# v0_1_0.net
KiCad netlist of a schematic drawn in EAGLE
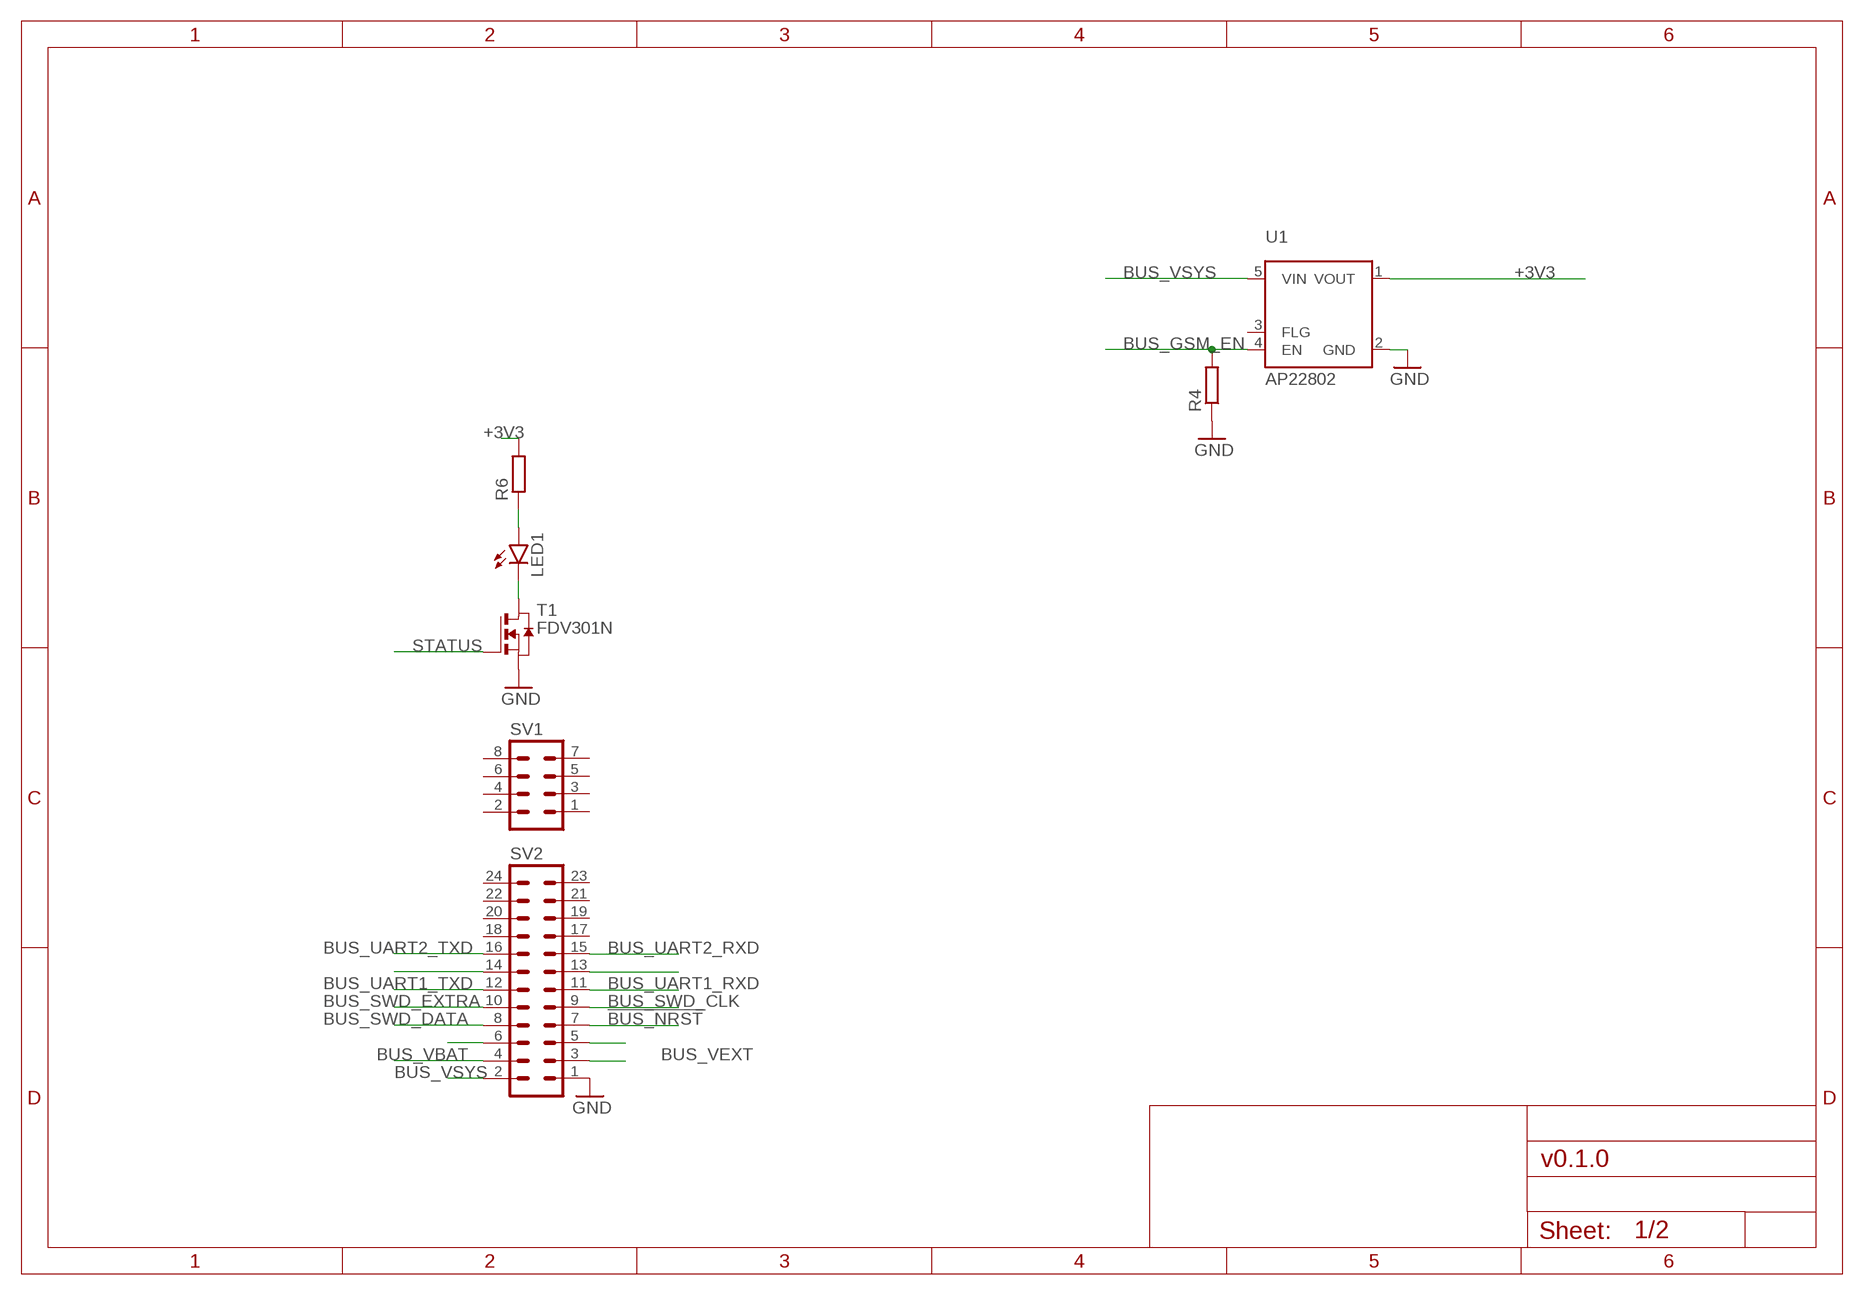
[diagram p0: schematic, sheet 1]
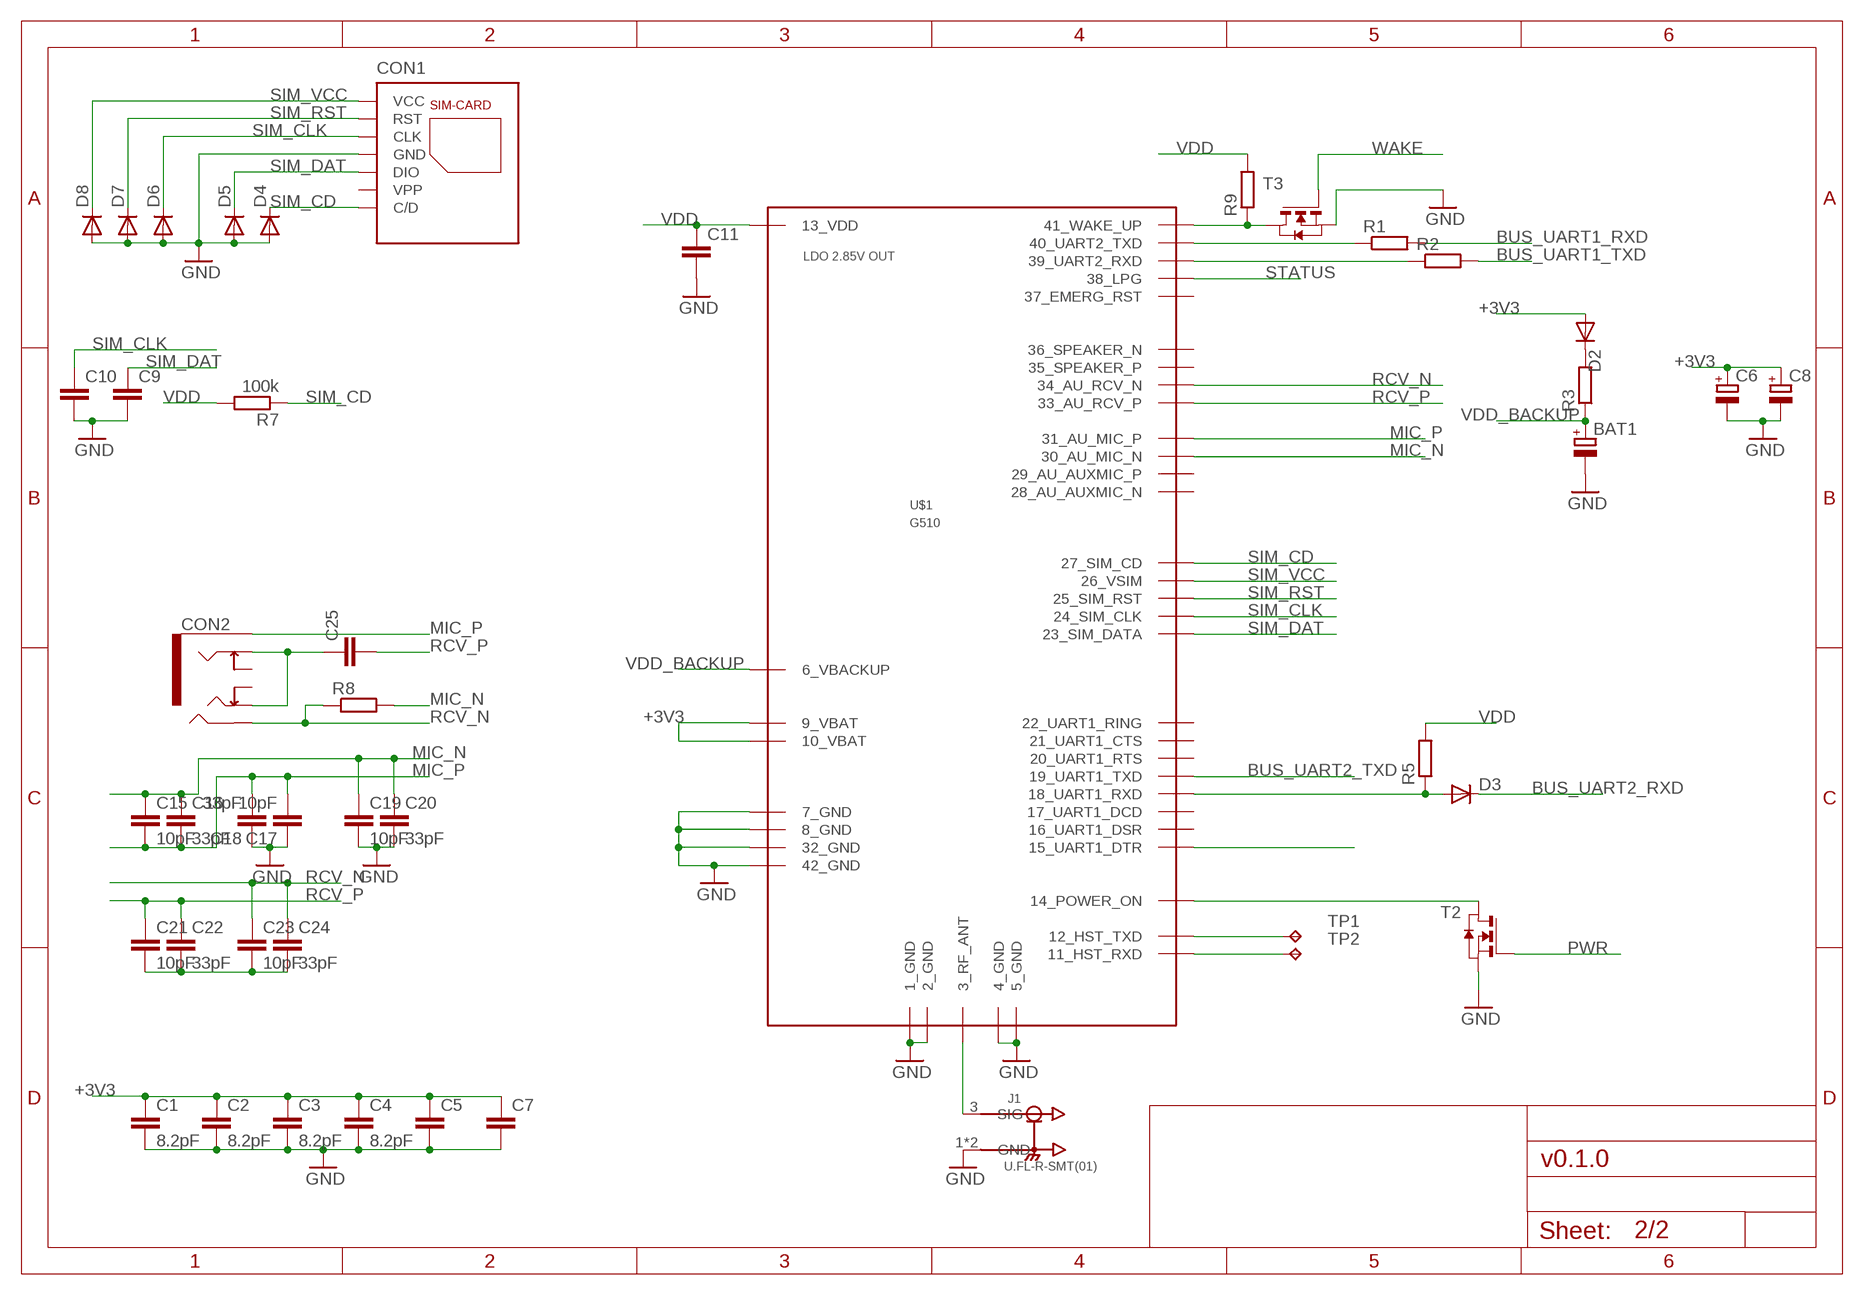
[diagram p1: schematic, sheet 2]

(export (version "E")
  (design (tool "Eeschema 10.0.6"))
  (components
    (comp (ref "LED1")
      (value "LEDCHIP-LED0603")
      (footprint "eagle-import:CHIP-LED0603")
      (libsource (lib "eagle-import") (part "LEDCHIP-LED0603"))
    )
    (comp (ref "R4")
      (value "R-EU_R0402")
      (footprint "eagle-import:R0402")
      (libsource (lib "eagle-import") (part "R-EU_R0402"))
    )
    (comp (ref "R6")
      (value "R-EU_R0402")
      (footprint "eagle-import:R0402")
      (libsource (lib "eagle-import") (part "R-EU_R0402"))
    )
    (comp (ref "SV1")
      (value "MA04-2")
      (footprint "eagle-import:MA04-2")
      (libsource (lib "eagle-import") (part "MA04-2"))
    )
    (comp (ref "SV2")
      (value "MA12-2")
      (footprint "eagle-import:MA12-2")
      (libsource (lib "eagle-import") (part "MA12-2"))
    )
    (comp (ref "T1")
      (value "FDV301N")
      (footprint "eagle-import:SOT-23")
      (libsource (lib "eagle-import") (part "NMOSSOT23"))
    )
    (comp (ref "U1")
      (value "AP22802")
      (footprint "eagle-import:SOT25")
      (libsource (lib "eagle-import") (part "AP22802"))
    )
    (comp (ref "BAT1")
      (value "DCK-3R3E224U-E")
      (footprint "eagle-import:621")
      (libsource (lib "eagle-import") (part "DCK-3R3E224U-E"))
    )
    (comp (ref "C1")
      (value "8.2pF")
      (footprint "eagle-import:C0402")
      (libsource (lib "eagle-import") (part "C-EUC0402"))
    )
    (comp (ref "C2")
      (value "8.2pF")
      (footprint "eagle-import:C0402")
      (libsource (lib "eagle-import") (part "C-EUC0402"))
    )
    (comp (ref "C3")
      (value "8.2pF")
      (footprint "eagle-import:C0402")
      (libsource (lib "eagle-import") (part "C-EUC0402"))
    )
    (comp (ref "C4")
      (value "8.2pF")
      (footprint "eagle-import:C0402")
      (libsource (lib "eagle-import") (part "C-EUC0402"))
    )
    (comp (ref "C5")
      (value "C-EUC0603")
      (footprint "eagle-import:C0603")
      (libsource (lib "eagle-import") (part "C-EUC0603"))
    )
    (comp (ref "C6")
      (value "CPOL-EUSMCC")
      (footprint "eagle-import:SMC_C")
      (libsource (lib "eagle-import") (part "CPOL-EUSMCC"))
    )
    (comp (ref "C7")
      (value "C-EUC0603")
      (footprint "eagle-import:C0603")
      (libsource (lib "eagle-import") (part "C-EUC0603"))
    )
    (comp (ref "C8")
      (value "CPOL-EUSMCC")
      (footprint "eagle-import:SMC_C")
      (libsource (lib "eagle-import") (part "CPOL-EUSMCC"))
    )
    (comp (ref "C9")
      (value "C-EUC0402")
      (footprint "eagle-import:C0402")
      (libsource (lib "eagle-import") (part "C-EUC0402"))
    )
    (comp (ref "C10")
      (value "C-EUC0402")
      (footprint "eagle-import:C0402")
      (libsource (lib "eagle-import") (part "C-EUC0402"))
    )
    (comp (ref "C11")
      (value "C-EUC0402")
      (footprint "eagle-import:C0402")
      (libsource (lib "eagle-import") (part "C-EUC0402"))
    )
    (comp (ref "C15")
      (value "10pF")
      (footprint "eagle-import:C0402")
      (libsource (lib "eagle-import") (part "C-EUC0402"))
    )
    (comp (ref "C16")
      (value "33pF")
      (footprint "eagle-import:C0402")
      (libsource (lib "eagle-import") (part "C-EUC0402"))
    )
    (comp (ref "C17")
      (value "10pF")
      (footprint "eagle-import:C0402")
      (libsource (lib "eagle-import") (part "C-EUC0402"))
    )
    (comp (ref "C18")
      (value "33pF")
      (footprint "eagle-import:C0402")
      (libsource (lib "eagle-import") (part "C-EUC0402"))
    )
    (comp (ref "C19")
      (value "10pF")
      (footprint "eagle-import:C0402")
      (libsource (lib "eagle-import") (part "C-EUC0402"))
    )
    (comp (ref "C20")
      (value "33pF")
      (footprint "eagle-import:C0402")
      (libsource (lib "eagle-import") (part "C-EUC0402"))
    )
    (comp (ref "C21")
      (value "10pF")
      (footprint "eagle-import:C0402")
      (libsource (lib "eagle-import") (part "C-EUC0402"))
    )
    (comp (ref "C22")
      (value "33pF")
      (footprint "eagle-import:C0402")
      (libsource (lib "eagle-import") (part "C-EUC0402"))
    )
    (comp (ref "C23")
      (value "10pF")
      (footprint "eagle-import:C0402")
      (libsource (lib "eagle-import") (part "C-EUC0402"))
    )
    (comp (ref "C24")
      (value "33pF")
      (footprint "eagle-import:C0402")
      (libsource (lib "eagle-import") (part "C-EUC0402"))
    )
    (comp (ref "C25")
      (value "C-EUC0603")
      (footprint "eagle-import:C0603")
      (libsource (lib "eagle-import") (part "C-EUC0603"))
    )
    (comp (ref "CON1")
      (value "115Q-BCA0")
      (footprint "eagle-import:115Q")
      (libsource (lib "eagle-import") (part "115Q-BCA0"))
    )
    (comp (ref "CON2")
      (value "1503-21")
      (footprint "eagle-import:150321")
      (libsource (lib "eagle-import") (part "1503-21"))
    )
    (comp (ref "D2")
      (value "DIODE-SOD323-R")
      (footprint "eagle-import:SOD323-R")
      (libsource (lib "eagle-import") (part "DIODE-SOD323-R"))
    )
    (comp (ref "D3")
      (value "DIODE-SOD323-R")
      (footprint "eagle-import:SOD323-R")
      (libsource (lib "eagle-import") (part "DIODE-SOD323-R"))
    )
    (comp (ref "D4")
      (value "DIODE-SOD323-R")
      (footprint "eagle-import:SOD323-R")
      (libsource (lib "eagle-import") (part "DIODE-SOD323-R"))
    )
    (comp (ref "D5")
      (value "DIODE-SOD323-R")
      (footprint "eagle-import:SOD323-R")
      (libsource (lib "eagle-import") (part "DIODE-SOD323-R"))
    )
    (comp (ref "D6")
      (value "DIODE-SOD323-R")
      (footprint "eagle-import:SOD323-R")
      (libsource (lib "eagle-import") (part "DIODE-SOD323-R"))
    )
    (comp (ref "D7")
      (value "DIODE-SOD323-R")
      (footprint "eagle-import:SOD323-R")
      (libsource (lib "eagle-import") (part "DIODE-SOD323-R"))
    )
    (comp (ref "D8")
      (value "DIODE-SOD323-R")
      (footprint "eagle-import:SOD323-R")
      (libsource (lib "eagle-import") (part "DIODE-SOD323-R"))
    )
    (comp (ref "J1")
      (value "U.FL-R-SMT(01)")
      (footprint "eagle-import:HRS_U.FL-R-SMT(01)")
      (fields (field (name "MF") "Hirose") (field (name "MP") "U.FL-R-SMT_01_"))
      (libsource (lib "eagle-import") (part "U.FL-R-SMT(01)"))
    )
    (comp (ref "R1")
      (value "R-EU_R0402")
      (footprint "eagle-import:R0402")
      (libsource (lib "eagle-import") (part "R-EU_R0402"))
    )
    (comp (ref "R2")
      (value "R-EU_R0402")
      (footprint "eagle-import:R0402")
      (libsource (lib "eagle-import") (part "R-EU_R0402"))
    )
    (comp (ref "R3")
      (value "R-EU_R0402")
      (footprint "eagle-import:R0402")
      (libsource (lib "eagle-import") (part "R-EU_R0402"))
    )
    (comp (ref "R5")
      (value "R-EU_R0402")
      (footprint "eagle-import:R0402")
      (libsource (lib "eagle-import") (part "R-EU_R0402"))
    )
    (comp (ref "R7")
      (value "100k")
      (footprint "eagle-import:R0402")
      (libsource (lib "eagle-import") (part "R-EU_R0402"))
    )
    (comp (ref "R8")
      (value "R-EU_R0402")
      (footprint "eagle-import:R0402")
      (libsource (lib "eagle-import") (part "R-EU_R0402"))
    )
    (comp (ref "R9")
      (value "R-EU_R0402")
      (footprint "eagle-import:R0402")
      (libsource (lib "eagle-import") (part "R-EU_R0402"))
    )
    (comp (ref "T2")
      (value "NMOSSOT23")
      (footprint "eagle-import:SOT-23")
      (libsource (lib "eagle-import") (part "NMOSSOT23"))
    )
    (comp (ref "T3")
      (value "NMOSSOT23")
      (footprint "eagle-import:SOT-23")
      (libsource (lib "eagle-import") (part "NMOSSOT23"))
    )
    (comp (ref "TP1")
      (value "TPB1,27")
      (footprint "eagle-import:B1,27")
      (libsource (lib "eagle-import") (part "TPB1,27"))
    )
    (comp (ref "TP2")
      (value "TPB1,27")
      (footprint "eagle-import:B1,27")
      (libsource (lib "eagle-import") (part "TPB1,27"))
    )
    (comp (ref "U$1")
      (value "G510")
      (footprint "eagle-import:G510")
      (libsource (lib "eagle-import") (part "G510"))
    )
  )
  (nets
    (net (code "1") (name "+3V3") (class "Default")
      (node (ref "C1") (pin "1") (pinfunction "1_1") (pintype "passive"))
      (node (ref "C2") (pin "1") (pinfunction "1_1") (pintype "passive"))
      (node (ref "C3") (pin "1") (pinfunction "1_1") (pintype "passive"))
      (node (ref "C4") (pin "1") (pinfunction "1_1") (pintype "passive"))
      (node (ref "C5") (pin "1") (pinfunction "1_1") (pintype "passive"))
      (node (ref "C6") (pin "+") (pinfunction "+_+") (pintype "passive"))
      (node (ref "C7") (pin "1") (pinfunction "1_1") (pintype "passive"))
      (node (ref "C8") (pin "+") (pinfunction "+_+") (pintype "passive"))
      (node (ref "D2") (pin "A") (pinfunction "A_A") (pintype "passive"))
      (node (ref "R6") (pin "2") (pinfunction "2_2") (pintype "passive"))
      (node (ref "U$1") (pin "10_VBAT") (pinfunction "10_VBAT_10_VBAT") (pintype "power_in"))
      (node (ref "U$1") (pin "9_VBAT") (pinfunction "9_VBAT_9_VBAT") (pintype "power_in"))
      (node (ref "U1") (pin "1") (pinfunction "VOUT_1") (pintype "bidirectional"))
    )
    (net (code "2") (name "BUS_GSM_EN") (class "Default")
      (node (ref "R4") (pin "2") (pinfunction "2_2") (pintype "passive"))
      (node (ref "U1") (pin "4") (pinfunction "EN_4") (pintype "bidirectional"))
    )
    (net (code "3") (name "BUS_SWD_CLK") (class "Default")
      (node (ref "SV2") (pin "9") (pinfunction "9_9") (pintype "passive"))
    )
    (net (code "4") (name "BUS_SWD_DATA") (class "Default")
      (node (ref "SV2") (pin "8") (pinfunction "8_8") (pintype "passive"))
    )
    (net (code "5") (name "BUS_SWD_EXTRA") (class "Default")
      (node (ref "SV2") (pin "10") (pinfunction "10_10") (pintype "passive"))
    )
    (net (code "6") (name "BUS_UART1_RXD") (class "Default")
      (node (ref "R1") (pin "2") (pinfunction "2_2") (pintype "passive"))
      (node (ref "SV2") (pin "11") (pinfunction "11_11") (pintype "passive"))
    )
    (net (code "7") (name "BUS_UART1_TXD") (class "Default")
      (node (ref "R2") (pin "2") (pinfunction "2_2") (pintype "passive"))
      (node (ref "SV2") (pin "12") (pinfunction "12_12") (pintype "passive"))
    )
    (net (code "8") (name "BUS_UART2_RXD") (class "Default")
      (node (ref "D3") (pin "C") (pinfunction "C_C") (pintype "passive"))
      (node (ref "SV2") (pin "15") (pinfunction "15_15") (pintype "passive"))
    )
    (net (code "9") (name "BUS_UART2_TXD") (class "Default")
      (node (ref "SV2") (pin "16") (pinfunction "16_16") (pintype "passive"))
      (node (ref "U$1") (pin "19_UART1_TXD") (pinfunction "19_UART1_TXD_19_UART1_TXD") (pintype "output"))
    )
    (net (code "10") (name "BUS_VBAT") (class "Default")
      (node (ref "SV2") (pin "4") (pinfunction "4_4") (pintype "passive"))
    )
    (net (code "11") (name "BUS_VEXT") (class "Default")
      (node (ref "SV2") (pin "3") (pinfunction "3_3") (pintype "passive"))
    )
    (net (code "12") (name "BUS_VSYS") (class "Default")
      (node (ref "SV2") (pin "2") (pinfunction "2_2") (pintype "passive"))
      (node (ref "U1") (pin "5") (pinfunction "VIN_5") (pintype "bidirectional"))
    )
    (net (code "13") (name "GND") (class "Default")
      (node (ref "BAT1") (pin "-") (pinfunction "-_-") (pintype "passive"))
      (node (ref "C1") (pin "2") (pinfunction "2_2") (pintype "passive"))
      (node (ref "C10") (pin "2") (pinfunction "2_2") (pintype "passive"))
      (node (ref "C11") (pin "2") (pinfunction "2_2") (pintype "passive"))
      (node (ref "C17") (pin "1") (pinfunction "1_1") (pintype "passive"))
      (node (ref "C18") (pin "1") (pinfunction "1_1") (pintype "passive"))
      (node (ref "C19") (pin "2") (pinfunction "2_2") (pintype "passive"))
      (node (ref "C2") (pin "2") (pinfunction "2_2") (pintype "passive"))
      (node (ref "C20") (pin "2") (pinfunction "2_2") (pintype "passive"))
      (node (ref "C3") (pin "2") (pinfunction "2_2") (pintype "passive"))
      (node (ref "C4") (pin "2") (pinfunction "2_2") (pintype "passive"))
      (node (ref "C5") (pin "2") (pinfunction "2_2") (pintype "passive"))
      (node (ref "C6") (pin "-") (pinfunction "-_-") (pintype "passive"))
      (node (ref "C7") (pin "2") (pinfunction "2_2") (pintype "passive"))
      (node (ref "C8") (pin "-") (pinfunction "-_-") (pintype "passive"))
      (node (ref "C9") (pin "2") (pinfunction "2_2") (pintype "passive"))
      (node (ref "CON1") (pin "GND1") (pinfunction "GND_GND1") (pintype "passive"))
      (node (ref "CON1") (pin "GND2") (pinfunction "GND_GND2") (pintype "passive"))
      (node (ref "CON1") (pin "GND3") (pinfunction "GND_GND3") (pintype "passive"))
      (node (ref "CON1") (pin "GND4") (pinfunction "GND_GND4") (pintype "passive"))
      (node (ref "CON1") (pin "P5") (pinfunction "GND_P5") (pintype "passive"))
      (node (ref "D4") (pin "A") (pinfunction "A_A") (pintype "passive"))
      (node (ref "D5") (pin "A") (pinfunction "A_A") (pintype "passive"))
      (node (ref "D6") (pin "A") (pinfunction "A_A") (pintype "passive"))
      (node (ref "D7") (pin "A") (pinfunction "A_A") (pintype "passive"))
      (node (ref "D8") (pin "A") (pinfunction "A_A") (pintype "passive"))
      (node (ref "J1") (pin "1") (pinfunction "GND_1") (pintype "passive"))
      (node (ref "J1") (pin "2") (pinfunction "GND_2") (pintype "passive"))
      (node (ref "R4") (pin "1") (pinfunction "1_1") (pintype "passive"))
      (node (ref "SV2") (pin "1") (pinfunction "1_1") (pintype "passive"))
      (node (ref "T1") (pin "2") (pinfunction "S_2") (pintype "passive"))
      (node (ref "T2") (pin "2") (pinfunction "S_2") (pintype "passive"))
      (node (ref "T3") (pin "2") (pinfunction "S_2") (pintype "passive"))
      (node (ref "U$1") (pin "1_GND") (pinfunction "1_GND_1_GND") (pintype "power_in"))
      (node (ref "U$1") (pin "2_GND") (pinfunction "2_GND_2_GND") (pintype "power_in"))
      (node (ref "U$1") (pin "32_GND") (pinfunction "32_GND_32_GND") (pintype "power_in"))
      (node (ref "U$1") (pin "42_GND") (pinfunction "42_GND_42_GND") (pintype "power_in"))
      (node (ref "U$1") (pin "4_GND") (pinfunction "4_GND_4_GND") (pintype "power_in"))
      (node (ref "U$1") (pin "5_GND") (pinfunction "5_GND_5_GND") (pintype "power_in"))
      (node (ref "U$1") (pin "7_GND") (pinfunction "7_GND_7_GND") (pintype "power_in"))
      (node (ref "U$1") (pin "8_GND") (pinfunction "8_GND_8_GND") (pintype "power_in"))
      (node (ref "U1") (pin "2") (pinfunction "GND_2") (pintype "bidirectional"))
    )
    (net (code "14") (name "MIC_N") (class "Default")
      (node (ref "C15") (pin "1") (pinfunction "1_1") (pintype "passive"))
      (node (ref "C16") (pin "1") (pinfunction "1_1") (pintype "passive"))
      (node (ref "C19") (pin "1") (pinfunction "1_1") (pintype "passive"))
      (node (ref "C20") (pin "1") (pinfunction "1_1") (pintype "passive"))
      (node (ref "R8") (pin "2") (pinfunction "2_2") (pintype "passive"))
      (node (ref "U$1") (pin "30_AU_MIC_N") (pinfunction "30_AU_MIC_N_30_AU_MIC_N") (pintype "bidirectional"))
    )
    (net (code "15") (name "MIC_P") (class "Default")
      (node (ref "C15") (pin "2") (pinfunction "2_2") (pintype "passive"))
      (node (ref "C16") (pin "2") (pinfunction "2_2") (pintype "passive"))
      (node (ref "C17") (pin "2") (pinfunction "2_2") (pintype "passive"))
      (node (ref "C18") (pin "2") (pinfunction "2_2") (pintype "passive"))
      (node (ref "CON2") (pin "1") (pinfunction "1_1") (pintype "bidirectional"))
      (node (ref "U$1") (pin "31_AU_MIC_P") (pinfunction "31_AU_MIC_P_31_AU_MIC_P") (pintype "bidirectional"))
    )
    (net (code "16") (name "Net-(C21-Pad2)") (class "Default")
      (node (ref "C21") (pin "2") (pinfunction "2_2") (pintype "passive"))
      (node (ref "C22") (pin "2") (pinfunction "2_2") (pintype "passive"))
      (node (ref "C23") (pin "2") (pinfunction "2_2") (pintype "passive"))
      (node (ref "C24") (pin "2") (pinfunction "2_2") (pintype "passive"))
    )
    (net (code "17") (name "Net-(C25-Pad1)") (class "Default")
      (node (ref "C25") (pin "1") (pinfunction "1_1") (pintype "passive"))
      (node (ref "CON2") (pin "3") (pinfunction "3_3") (pintype "bidirectional"))
      (node (ref "CON2") (pin "5") (pinfunction "5_5") (pintype "bidirectional"))
    )
    (net (code "18") (name "Net-(D2-PadC)") (class "Default")
      (node (ref "D2") (pin "C") (pinfunction "C_C") (pintype "passive"))
      (node (ref "R3") (pin "2") (pinfunction "2_2") (pintype "passive"))
    )
    (net (code "19") (name "Net-(D3-PadA)") (class "Default")
      (node (ref "D3") (pin "A") (pinfunction "A_A") (pintype "passive"))
      (node (ref "R5") (pin "1") (pinfunction "1_1") (pintype "passive"))
      (node (ref "U$1") (pin "18_UART1_RXD") (pinfunction "18_UART1_RXD_18_UART1_RXD") (pintype "input"))
    )
    (net (code "20") (name "Net-(J1-SIG)") (class "Default")
      (node (ref "J1") (pin "3") (pinfunction "SIG_3") (pintype "passive"))
      (node (ref "U$1") (pin "3_RF_ANT") (pinfunction "3_RF_ANT_3_RF_ANT") (pintype "bidirectional"))
    )
    (net (code "21") (name "Net-(LED1-PadA)") (class "Default")
      (node (ref "LED1") (pin "A") (pinfunction "A_A") (pintype "passive"))
      (node (ref "R6") (pin "1") (pinfunction "1_1") (pintype "passive"))
    )
    (net (code "22") (name "Net-(R1-Pad1)") (class "Default")
      (node (ref "R1") (pin "1") (pinfunction "1_1") (pintype "passive"))
      (node (ref "U$1") (pin "40_UART2_TXD") (pinfunction "40_UART2_TXD_40_UART2_TXD") (pintype "output"))
    )
    (net (code "23") (name "Net-(R2-Pad1)") (class "Default")
      (node (ref "R2") (pin "1") (pinfunction "1_1") (pintype "passive"))
      (node (ref "U$1") (pin "39_UART2_RXD") (pinfunction "39_UART2_RXD_39_UART2_RXD") (pintype "input"))
    )
    (net (code "24") (name "Net-(T1-D)") (class "Default")
      (node (ref "LED1") (pin "C") (pinfunction "C_C") (pintype "passive"))
      (node (ref "T1") (pin "1") (pinfunction "D_1") (pintype "passive"))
    )
    (net (code "25") (name "Net-(T2-D)") (class "Default")
      (node (ref "T2") (pin "1") (pinfunction "D_1") (pintype "passive"))
      (node (ref "U$1") (pin "14_POWER_ON") (pinfunction "14_POWER_ON_14_POWER_ON") (pintype "input"))
    )
    (net (code "26") (name "Net-(T3-D)") (class "Default")
      (node (ref "R9") (pin "1") (pinfunction "1_1") (pintype "passive"))
      (node (ref "T3") (pin "1") (pinfunction "D_1") (pintype "passive"))
      (node (ref "U$1") (pin "41_WAKE_UP") (pinfunction "41_WAKE_UP_41_WAKE_UP") (pintype "bidirectional"))
    )
    (net (code "27") (name "Net-(TP1-PadTP)") (class "Default")
      (node (ref "TP1") (pin "TP") (pinfunction "TP_TP") (pintype "input"))
      (node (ref "U$1") (pin "12_HST_TXD") (pinfunction "12_HST_TXD_12_HST_TXD") (pintype "output"))
    )
    (net (code "28") (name "Net-(U$1-11_HST_RXD)") (class "Default")
      (node (ref "TP2") (pin "TP") (pinfunction "TP_TP") (pintype "input"))
      (node (ref "U$1") (pin "11_HSTRXD") (pinfunction "11_HST_RXD_11_HSTRXD") (pintype "input"))
    )
    (net (code "29") (name "PWR") (class "Default")
      (node (ref "T2") (pin "3") (pinfunction "G_3") (pintype "passive"))
    )
    (net (code "30") (name "RCV_N") (class "Default")
      (node (ref "C23") (pin "1") (pinfunction "1_1") (pintype "passive"))
      (node (ref "C24") (pin "1") (pinfunction "1_1") (pintype "passive"))
      (node (ref "CON2") (pin "2") (pinfunction "2_2") (pintype "bidirectional"))
      (node (ref "R8") (pin "1") (pinfunction "1_1") (pintype "passive"))
      (node (ref "U$1") (pin "34_AU_RCV_N") (pinfunction "34_AU_RCV_N_34_AU_RCV_N") (pintype "bidirectional"))
    )
    (net (code "31") (name "RCV_P") (class "Default")
      (node (ref "C21") (pin "1") (pinfunction "1_1") (pintype "passive"))
      (node (ref "C22") (pin "1") (pinfunction "1_1") (pintype "passive"))
      (node (ref "C25") (pin "2") (pinfunction "2_2") (pintype "passive"))
      (node (ref "U$1") (pin "33_AU_RCV_P") (pinfunction "33_AU_RCV_P_33_AU_RCV_P") (pintype "bidirectional"))
    )
    (net (code "32") (name "SIM_CD") (class "Default")
      (node (ref "CON1") (pin "CD") (pinfunction "C/D_CD") (pintype "passive"))
      (node (ref "D4") (pin "C") (pinfunction "C_C") (pintype "passive"))
      (node (ref "R7") (pin "1") (pinfunction "1_1") (pintype "passive"))
      (node (ref "U$1") (pin "27_SIM_CD") (pinfunction "27_SIM_CD_27_SIM_CD") (pintype "bidirectional"))
    )
    (net (code "33") (name "SIM_CLK") (class "Default")
      (node (ref "C10") (pin "1") (pinfunction "1_1") (pintype "passive"))
      (node (ref "CON1") (pin "P3") (pinfunction "CLK_P3") (pintype "passive"))
      (node (ref "D6") (pin "C") (pinfunction "C_C") (pintype "passive"))
      (node (ref "U$1") (pin "24_SIM_CLK") (pinfunction "24_SIM_CLK_24_SIM_CLK") (pintype "bidirectional"))
    )
    (net (code "34") (name "SIM_DAT") (class "Default")
      (node (ref "C9") (pin "1") (pinfunction "1_1") (pintype "passive"))
      (node (ref "CON1") (pin "P7") (pinfunction "DIO_P7") (pintype "passive"))
      (node (ref "D5") (pin "C") (pinfunction "C_C") (pintype "passive"))
      (node (ref "U$1") (pin "23_SIM_DATA") (pinfunction "23_SIM_DATA_23_SIM_DATA") (pintype "bidirectional"))
    )
    (net (code "35") (name "SIM_RST") (class "Default")
      (node (ref "CON1") (pin "P2") (pinfunction "RST_P2") (pintype "passive"))
      (node (ref "D7") (pin "C") (pinfunction "C_C") (pintype "passive"))
      (node (ref "U$1") (pin "25_SIM_RST") (pinfunction "25_SIM_RST_25_SIM_RST") (pintype "bidirectional"))
    )
    (net (code "36") (name "SIM_VCC") (class "Default")
      (node (ref "CON1") (pin "P1") (pinfunction "VCC_P1") (pintype "passive"))
      (node (ref "D8") (pin "C") (pinfunction "C_C") (pintype "passive"))
      (node (ref "U$1") (pin "26_VSIM") (pinfunction "26_VSIM_26_VSIM") (pintype "bidirectional"))
    )
    (net (code "37") (name "STATUS") (class "Default")
      (node (ref "T1") (pin "3") (pinfunction "G_3") (pintype "passive"))
      (node (ref "U$1") (pin "38_LPG") (pinfunction "38_LPG_38_LPG") (pintype "output"))
    )
    (net (code "38") (name "VDD") (class "Default")
      (node (ref "C11") (pin "1") (pinfunction "1_1") (pintype "passive"))
      (node (ref "R5") (pin "2") (pinfunction "2_2") (pintype "passive"))
      (node (ref "R7") (pin "2") (pinfunction "2_2") (pintype "passive"))
      (node (ref "R9") (pin "2") (pinfunction "2_2") (pintype "passive"))
      (node (ref "U$1") (pin "13_VDD") (pinfunction "13_VDD_13_VDD") (pintype "power_in"))
    )
    (net (code "39") (name "VDD_BACKUP") (class "Default")
      (node (ref "BAT1") (pin "+") (pinfunction "+_+") (pintype "passive"))
      (node (ref "R3") (pin "1") (pinfunction "1_1") (pintype "passive"))
      (node (ref "U$1") (pin "6_VBACKUP") (pinfunction "6_VBACKUP_6_VBACKUP") (pintype "power_in"))
    )
    (net (code "40") (name "WAKE") (class "Default")
      (node (ref "T3") (pin "3") (pinfunction "G_3") (pintype "passive"))
    )
    (net (code "41") (name "unconnected-(CON1-VPP-PadP6)") (class "Default")
      (node (ref "CON1") (pin "P6") (pinfunction "VPP_P6") (pintype "passive"))
    )
    (net (code "42") (name "unconnected-(CON2-Pad4)") (class "Default")
      (node (ref "CON2") (pin "4") (pinfunction "4_4") (pintype "bidirectional"))
    )
    (net (code "43") (name "unconnected-(CON2-Pad6)") (class "Default")
      (node (ref "CON2") (pin "6") (pinfunction "6_6") (pintype "bidirectional"))
    )
    (net (code "44") (name "unconnected-(SV1-Pad1)") (class "Default")
      (node (ref "SV1") (pin "1") (pinfunction "1_1") (pintype "passive"))
    )
    (net (code "45") (name "unconnected-(SV1-Pad2)") (class "Default")
      (node (ref "SV1") (pin "2") (pinfunction "2_2") (pintype "passive"))
    )
    (net (code "46") (name "unconnected-(SV1-Pad3)") (class "Default")
      (node (ref "SV1") (pin "3") (pinfunction "3_3") (pintype "passive"))
    )
    (net (code "47") (name "unconnected-(SV1-Pad4)") (class "Default")
      (node (ref "SV1") (pin "4") (pinfunction "4_4") (pintype "passive"))
    )
    (net (code "48") (name "unconnected-(SV1-Pad5)") (class "Default")
      (node (ref "SV1") (pin "5") (pinfunction "5_5") (pintype "passive"))
    )
    (net (code "49") (name "unconnected-(SV1-Pad6)") (class "Default")
      (node (ref "SV1") (pin "6") (pinfunction "6_6") (pintype "passive"))
    )
    (net (code "50") (name "unconnected-(SV1-Pad7)") (class "Default")
      (node (ref "SV1") (pin "7") (pinfunction "7_7") (pintype "passive"))
    )
    (net (code "51") (name "unconnected-(SV1-Pad8)") (class "Default")
      (node (ref "SV1") (pin "8") (pinfunction "8_8") (pintype "passive"))
    )
    (net (code "52") (name "unconnected-(SV2-Pad5)") (class "Default")
      (node (ref "SV2") (pin "5") (pinfunction "5_5") (pintype "passive"))
    )
    (net (code "53") (name "unconnected-(SV2-Pad6)") (class "Default")
      (node (ref "SV2") (pin "6") (pinfunction "6_6") (pintype "passive"))
    )
    (net (code "54") (name "unconnected-(SV2-Pad13)") (class "Default")
      (node (ref "SV2") (pin "13") (pinfunction "13_13") (pintype "passive"))
    )
    (net (code "55") (name "unconnected-(SV2-Pad14)") (class "Default")
      (node (ref "SV2") (pin "14") (pinfunction "14_14") (pintype "passive"))
    )
    (net (code "56") (name "unconnected-(SV2-Pad17)") (class "Default")
      (node (ref "SV2") (pin "17") (pinfunction "17_17") (pintype "passive"))
    )
    (net (code "57") (name "unconnected-(SV2-Pad18)") (class "Default")
      (node (ref "SV2") (pin "18") (pinfunction "18_18") (pintype "passive"))
    )
    (net (code "58") (name "unconnected-(SV2-Pad19)") (class "Default")
      (node (ref "SV2") (pin "19") (pinfunction "19_19") (pintype "passive"))
    )
    (net (code "59") (name "unconnected-(SV2-Pad20)") (class "Default")
      (node (ref "SV2") (pin "20") (pinfunction "20_20") (pintype "passive"))
    )
    (net (code "60") (name "unconnected-(SV2-Pad21)") (class "Default")
      (node (ref "SV2") (pin "21") (pinfunction "21_21") (pintype "passive"))
    )
    (net (code "61") (name "unconnected-(SV2-Pad22)") (class "Default")
      (node (ref "SV2") (pin "22") (pinfunction "22_22") (pintype "passive"))
    )
    (net (code "62") (name "unconnected-(SV2-Pad23)") (class "Default")
      (node (ref "SV2") (pin "23") (pinfunction "23_23") (pintype "passive"))
    )
    (net (code "63") (name "unconnected-(SV2-Pad24)") (class "Default")
      (node (ref "SV2") (pin "24") (pinfunction "24_24") (pintype "passive"))
    )
    (net (code "64") (name "unconnected-(U$1-Pad15_UART1_DTR)") (class "Default")
      (node (ref "U$1") (pin "15_UART1_DTR") (pinfunction "15_UART1_DTR_15_UART1_DTR") (pintype "bidirectional"))
    )
    (net (code "65") (name "unconnected-(U$1-Pad16_UART1_DSR)") (class "Default")
      (node (ref "U$1") (pin "16_UART1_DSR") (pinfunction "16_UART1_DSR_16_UART1_DSR") (pintype "bidirectional"))
    )
    (net (code "66") (name "unconnected-(U$1-Pad17_UART1_DCD)") (class "Default")
      (node (ref "U$1") (pin "17_UART1_DCD") (pinfunction "17_UART1_DCD_17_UART1_DCD") (pintype "bidirectional"))
    )
    (net (code "67") (name "unconnected-(U$1-Pad20_UART1_RTS)") (class "Default")
      (node (ref "U$1") (pin "20_UART1_RTS") (pinfunction "20_UART1_RTS_20_UART1_RTS") (pintype "bidirectional"))
    )
    (net (code "68") (name "unconnected-(U$1-Pad21_UART1_CTS)") (class "Default")
      (node (ref "U$1") (pin "21_UART1_CTS") (pinfunction "21_UART1_CTS_21_UART1_CTS") (pintype "bidirectional"))
    )
    (net (code "69") (name "unconnected-(U$1-Pad22_UART1_RING)") (class "Default")
      (node (ref "U$1") (pin "22_UART1_RING") (pinfunction "22_UART1_RING_22_UART1_RING") (pintype "bidirectional"))
    )
    (net (code "70") (name "unconnected-(U$1-Pad28_AU_AUXMIC_N)") (class "Default")
      (node (ref "U$1") (pin "28_AU_AUXMIC_N") (pinfunction "28_AU_AUXMIC_N_28_AU_AUXMIC_N") (pintype "bidirectional"))
    )
    (net (code "71") (name "unconnected-(U$1-Pad29_AU_AUXMIC_P)") (class "Default")
      (node (ref "U$1") (pin "29_AU_AUXMIC_P") (pinfunction "29_AU_AUXMIC_P_29_AU_AUXMIC_P") (pintype "bidirectional"))
    )
    (net (code "72") (name "unconnected-(U$1-Pad35_SPEAKER_P)") (class "Default")
      (node (ref "U$1") (pin "35_SPEAKER_P") (pinfunction "35_SPEAKER_P_35_SPEAKER_P") (pintype "bidirectional"))
    )
    (net (code "73") (name "unconnected-(U$1-Pad36_SPEAKER_N)") (class "Default")
      (node (ref "U$1") (pin "36_SPEAKER_N") (pinfunction "36_SPEAKER_N_36_SPEAKER_N") (pintype "bidirectional"))
    )
    (net (code "74") (name "unconnected-(U$1-Pad37_EMERG_RST)") (class "Default")
      (node (ref "U$1") (pin "37_EMERG_RST") (pinfunction "37_EMERG_RST_37_EMERG_RST") (pintype "input"))
    )
    (net (code "75") (name "unconnected-(U1-FLG-Pad3)") (class "Default")
      (node (ref "U1") (pin "3") (pinfunction "FLG_3") (pintype "bidirectional"))
    )
    (net (code "76") (name "~{BUS_NRST}") (class "Default")
      (node (ref "SV2") (pin "7") (pinfunction "7_7") (pintype "passive"))
    )
  )
)
